# 06_-_WI-FI_MODULE.net
KiCad netlist of a schematic drawn in Altium Designer
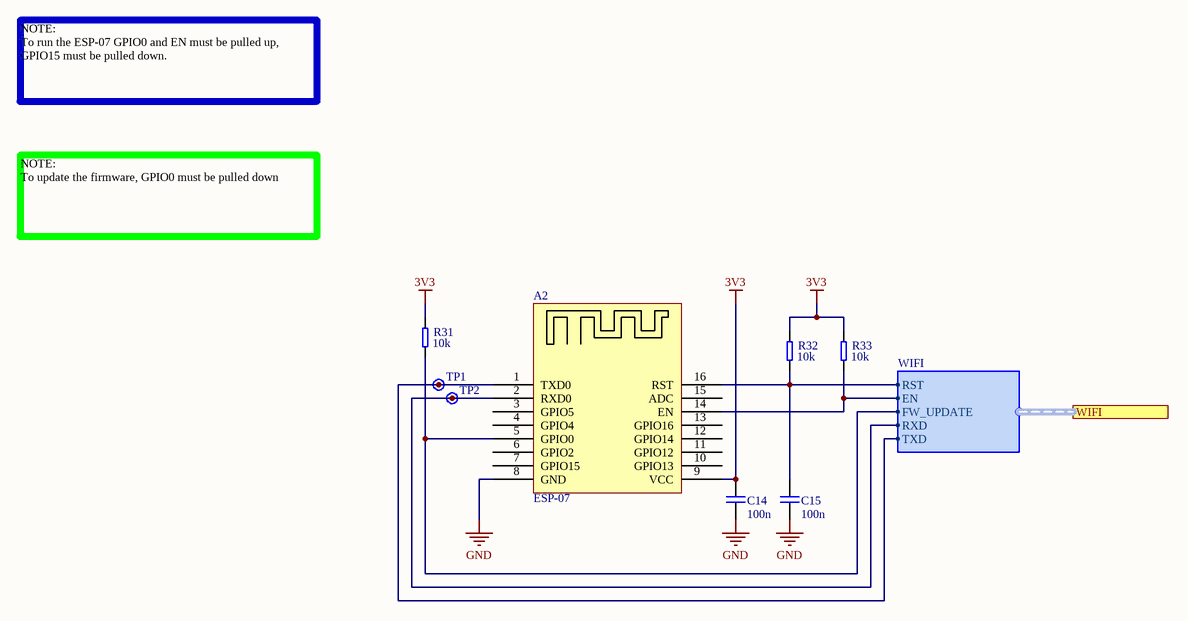
[diagram p0: [06] - WI-FI MODULE.SchDoc]

(export (version "E")
  (design (tool "Eeschema 10.0.6"))
  (components
    (comp (ref "A2")
      (value "ESP-07")
      (description "ESP8266 WIFI 802.11B/G/N 160MBIT")
      (fields (field (name "MANUFACTURER") "AI Thinker"))
      (libsource (lib "1") (part "ESP-07"))
    )
    (comp (ref "C14") (value "100n") (description "CAPACITOR") (libsource (lib "1") (part "Cap")))
    (comp (ref "C15") (value "100n") (description "CAPACITOR") (libsource (lib "1") (part "Cap")))
    (comp (ref "R31") (value "10k") (description "RESISTOR") (libsource (lib "1") (part "Res")))
    (comp (ref "R32") (value "10k") (description "RESISTOR") (libsource (lib "1") (part "Res")))
    (comp (ref "R33") (value "10k") (description "RESISTOR") (libsource (lib "1") (part "Res")))
    (comp (ref "TP1")
      (value "Test Point")
      (description "Test point")
      (libsource (lib "1") (part "Test Point"))
    )
    (comp (ref "TP2")
      (value "Test Point")
      (description "Test point")
      (libsource (lib "1") (part "Test Point"))
    )
  )
  (nets
    (net (code "3") (name "3V3") (class "Default")
      (node (ref "A2") (pin "9") (pinfunction "VCC_9") (pintype "passive"))
      (node (ref "C14") (pin "2") (pinfunction "2_2") (pintype "passive"))
      (node (ref "R31") (pin "2") (pinfunction "2_2") (pintype "passive"))
      (node (ref "R32") (pin "2") (pinfunction "2_2") (pintype "passive"))
      (node (ref "R33") (pin "2") (pinfunction "2_2") (pintype "passive"))
    )
    (net (code "4") (name "GND") (class "Default")
      (node (ref "A2") (pin "8") (pinfunction "GND_8") (pintype "passive"))
      (node (ref "C14") (pin "1") (pinfunction "1_1") (pintype "passive"))
      (node (ref "C15") (pin "1") (pinfunction "1_1") (pintype "passive"))
    )
    (net (code "5") (name "Net-(A2-EN)") (class "Default")
      (node (ref "A2") (pin "14") (pinfunction "EN_14") (pintype "passive"))
      (node (ref "R33") (pin "1") (pinfunction "1_1") (pintype "passive"))
    )
    (net (code "6") (name "Net-(A2-GPIO0)") (class "Default")
      (node (ref "A2") (pin "5") (pinfunction "GPIO0_5") (pintype "passive"))
      (node (ref "R31") (pin "1") (pinfunction "1_1") (pintype "passive"))
    )
    (net (code "7") (name "Net-(A2-RST)") (class "Default")
      (node (ref "A2") (pin "16") (pinfunction "RST_16") (pintype "passive"))
      (node (ref "C15") (pin "2") (pinfunction "2_2") (pintype "passive"))
      (node (ref "R32") (pin "1") (pinfunction "1_1") (pintype "passive"))
    )
    (net (code "8") (name "Net-(A2-RXD0)") (class "Default")
      (node (ref "A2") (pin "2") (pinfunction "RXD0_2") (pintype "passive"))
      (node (ref "TP2") (pin "1") (pinfunction "1_1") (pintype "passive"))
    )
    (net (code "9") (name "Net-(A2-TXD0)") (class "Default")
      (node (ref "A2") (pin "1") (pinfunction "TXD0_1") (pintype "passive"))
      (node (ref "TP1") (pin "1") (pinfunction "1_1") (pintype "passive"))
    )
    (net (code "10") (name "unconnected-(A2-ADC-Pad15)") (class "Default")
      (node (ref "A2") (pin "15") (pinfunction "ADC_15") (pintype "passive"))
    )
    (net (code "11") (name "unconnected-(A2-GPIO2-Pad6)") (class "Default")
      (node (ref "A2") (pin "6") (pinfunction "GPIO2_6") (pintype "passive"))
    )
    (net (code "12") (name "unconnected-(A2-GPIO4-Pad4)") (class "Default")
      (node (ref "A2") (pin "4") (pinfunction "GPIO4_4") (pintype "passive"))
    )
    (net (code "13") (name "unconnected-(A2-GPIO5-Pad3)") (class "Default")
      (node (ref "A2") (pin "3") (pinfunction "GPIO5_3") (pintype "passive"))
    )
    (net (code "14") (name "unconnected-(A2-GPIO12-Pad11)") (class "Default")
      (node (ref "A2") (pin "11") (pinfunction "GPIO12_11") (pintype "passive"))
    )
    (net (code "15") (name "unconnected-(A2-GPIO13-Pad10)") (class "Default")
      (node (ref "A2") (pin "10") (pinfunction "GPIO13_10") (pintype "passive"))
    )
    (net (code "16") (name "unconnected-(A2-GPIO14-Pad12)") (class "Default")
      (node (ref "A2") (pin "12") (pinfunction "GPIO14_12") (pintype "passive"))
    )
    (net (code "17") (name "unconnected-(A2-GPIO15-Pad7)") (class "Default")
      (node (ref "A2") (pin "7") (pinfunction "GPIO15_7") (pintype "passive"))
    )
    (net (code "18") (name "unconnected-(A2-GPIO16-Pad13)") (class "Default")
      (node (ref "A2") (pin "13") (pinfunction "GPIO16_13") (pintype "passive"))
    )
  )
)
